# PocaSynth.net
KiCad netlist of a schematic drawn in EAGLE
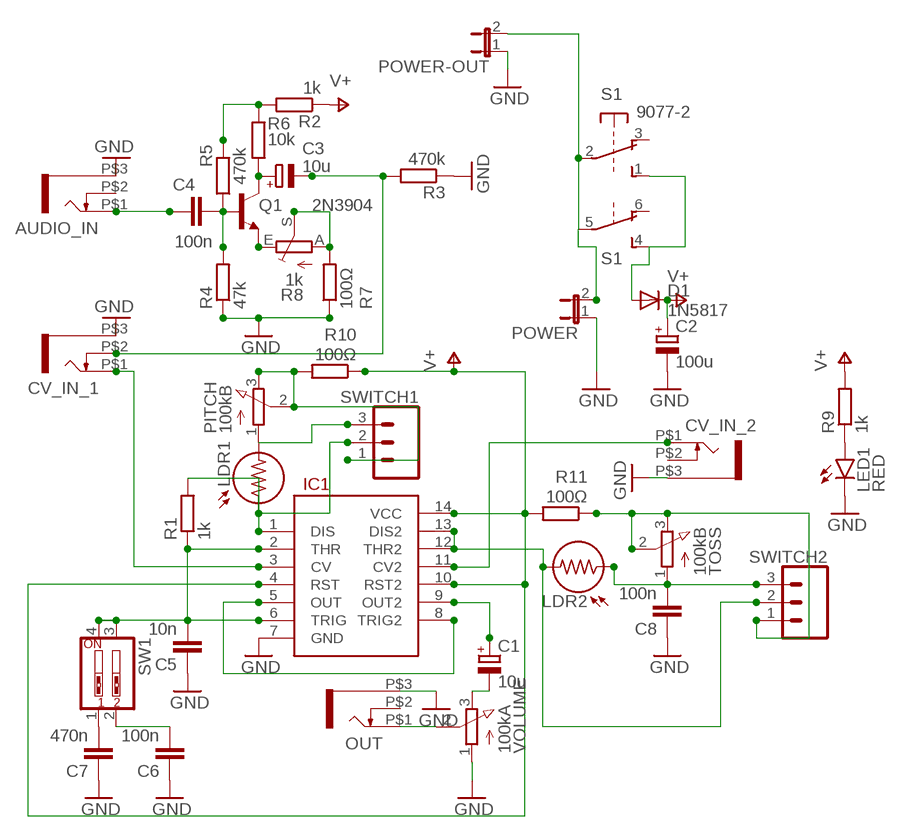
[diagram p0: schematic, sheet 1]

(export (version "E")
  (design (tool "Eeschema 10.0.6"))
  (components
    (comp (ref "AUDIO_IN")
      (value "WQP-PJ301M-12_JACK")
      (footprint "eagle-import:WQP-PJ301M-12_JACK")
      (libsource (lib "eagle-import") (part "WQP-PJ301M-12_JACK"))
    )
    (comp (ref "C1")
      (value "10u")
      (footprint "eagle-import:E2,5-7")
      (libsource (lib "eagle-import") (part "CPOL-EUE2.5-7"))
    )
    (comp (ref "C2")
      (value "100u")
      (footprint "eagle-import:E2,5-7")
      (libsource (lib "eagle-import") (part "CPOL-EUE2.5-7"))
    )
    (comp (ref "C3")
      (value "10u")
      (footprint "eagle-import:E2,5-7")
      (libsource (lib "eagle-import") (part "CPOL-EUE2.5-7"))
    )
    (comp (ref "C4")
      (value "100n")
      (footprint "eagle-import:C050-035X075")
      (libsource (lib "eagle-import") (part "C-EU050-035X075"))
    )
    (comp (ref "C5")
      (value "10n")
      (footprint "eagle-import:C050-030X075")
      (libsource (lib "eagle-import") (part "C-EU050-030X075"))
    )
    (comp (ref "C6")
      (value "100n")
      (footprint "eagle-import:C050-030X075")
      (libsource (lib "eagle-import") (part "C-EU050-030X075"))
    )
    (comp (ref "C7")
      (value "470n")
      (footprint "eagle-import:C050-035X075")
      (libsource (lib "eagle-import") (part "C-EU050-035X075"))
    )
    (comp (ref "C8")
      (value "100n")
      (footprint "eagle-import:C050-030X075")
      (libsource (lib "eagle-import") (part "C-EU050-030X075"))
    )
    (comp (ref "CV_IN_1")
      (value "WQP-PJ301M-12_JACK")
      (footprint "eagle-import:WQP-PJ301M-12_JACK")
      (libsource (lib "eagle-import") (part "WQP-PJ301M-12_JACK"))
    )
    (comp (ref "CV_IN_2")
      (value "WQP-PJ301M-12_JACK")
      (footprint "eagle-import:WQP-PJ301M-12_JACK")
      (libsource (lib "eagle-import") (part "WQP-PJ301M-12_JACK"))
    )
    (comp (ref "D1")
      (value "1N5817")
      (footprint "eagle-import:DO41-10")
      (libsource (lib "eagle-import") (part "1N4004"))
    )
    (comp (ref "IC1")
      (value "556")
      (footprint "eagle-import:DIL14")
      (libsource (lib "eagle-import") (part "556"))
    )
    (comp (ref "LDR1")
      (value "LDR5MM")
      (footprint "eagle-import:LDR338-54C")
      (libsource (lib "eagle-import") (part "LDR5MM"))
    )
    (comp (ref "LDR2")
      (value "LDR5MM")
      (footprint "eagle-import:LDR338-54C")
      (libsource (lib "eagle-import") (part "LDR5MM"))
    )
    (comp (ref "LED1")
      (value "RED")
      (footprint "eagle-import:LED3MM")
      (libsource (lib "eagle-import") (part "LED3MM"))
    )
    (comp (ref "OUT")
      (value "WQP-PJ301M-12_JACK")
      (footprint "eagle-import:WQP-PJ301M-12_JACK")
      (libsource (lib "eagle-import") (part "WQP-PJ301M-12_JACK"))
    )
    (comp (ref "PITCH")
      (value "100kB")
      (footprint "eagle-import:EVUFXM")
      (libsource (lib "eagle-import") (part "EVUMF3"))
    )
    (comp (ref "POWER")
      (value "JP1E")
      (footprint "eagle-import:JP1")
      (libsource (lib "eagle-import") (part "JP1E"))
    )
    (comp (ref "POWER-OUT")
      (value "JP1E")
      (footprint "eagle-import:JP1")
      (libsource (lib "eagle-import") (part "JP1E"))
    )
    (comp (ref "Q1")
      (value "2N3904")
      (footprint "eagle-import:TO92-")
      (libsource (lib "eagle-import") (part "2N3904"))
    )
    (comp (ref "R1")
      (value "1k")
      (footprint "eagle-import:0207_10")
      (libsource (lib "eagle-import") (part "R-EU_0207/10"))
    )
    (comp (ref "R2")
      (value "1k")
      (footprint "eagle-import:0207_10")
      (libsource (lib "eagle-import") (part "R-EU_0207/10"))
    )
    (comp (ref "R3")
      (value "470k")
      (footprint "eagle-import:0207_10")
      (libsource (lib "eagle-import") (part "R-EU_0207/10"))
    )
    (comp (ref "R4")
      (value "47k")
      (footprint "eagle-import:0207_10")
      (libsource (lib "eagle-import") (part "R-EU_0207/10"))
    )
    (comp (ref "R5")
      (value "470k")
      (footprint "eagle-import:0207_10")
      (libsource (lib "eagle-import") (part "R-EU_0207/10"))
    )
    (comp (ref "R6")
      (value "10k")
      (footprint "eagle-import:0207_10")
      (libsource (lib "eagle-import") (part "R-EU_0207/10"))
    )
    (comp (ref "R7")
      (value "100Ω")
      (footprint "eagle-import:0207_10")
      (libsource (lib "eagle-import") (part "R-EU_0207/10"))
    )
    (comp (ref "R8")
      (value "1k")
      (footprint "eagle-import:CA6V")
      (libsource (lib "eagle-import") (part "TRIM_EU-CA6V"))
    )
    (comp (ref "R9")
      (value "1k")
      (footprint "eagle-import:0207_10")
      (libsource (lib "eagle-import") (part "R-EU_0207/10"))
    )
    (comp (ref "R10")
      (value "100Ω")
      (footprint "eagle-import:0207_10")
      (libsource (lib "eagle-import") (part "R-EU_0207/10"))
    )
    (comp (ref "R11")
      (value "100Ω")
      (footprint "eagle-import:0207_10")
      (libsource (lib "eagle-import") (part "R-EU_0207/10"))
    )
    (comp (ref "S1")
      (value "9077-2")
      (footprint "eagle-import:9077-2")
      (libsource (lib "eagle-import") (part "9077-2"))
    )
    (comp (ref "SW1")
      (value "SW_DIP-2")
      (footprint "eagle-import:EDG-02")
      (libsource (lib "eagle-import") (part "SW_DIP-2"))
    )
    (comp (ref "SWITCH1")
      (value "CONN_03LOCK")
      (footprint "eagle-import:1X03_LOCK")
      (libsource (lib "eagle-import") (part "CONN_03LOCK"))
    )
    (comp (ref "SWITCH2")
      (value "CONN_03LOCK")
      (footprint "eagle-import:1X03_LOCK")
      (libsource (lib "eagle-import") (part "CONN_03LOCK"))
    )
    (comp (ref "TOSS")
      (value "100kB")
      (footprint "eagle-import:EVUFXM")
      (libsource (lib "eagle-import") (part "EVUMF3"))
    )
    (comp (ref "VOLUME")
      (value "100kA")
      (footprint "eagle-import:EVUFXM")
      (libsource (lib "eagle-import") (part "EVUMF3"))
    )
  )
  (nets
    (net (code "1") (name "GND") (class "Default")
      (node (ref "AUDIO_IN") (pin "P$3") (pinfunction "1_P$3") (pintype "passive"))
      (node (ref "C2") (pin "-") (pinfunction "-_-") (pintype "passive"))
      (node (ref "C5") (pin "1") (pinfunction "1_1") (pintype "passive"))
      (node (ref "C6") (pin "1") (pinfunction "1_1") (pintype "passive"))
      (node (ref "C7") (pin "1") (pinfunction "1_1") (pintype "passive"))
      (node (ref "C8") (pin "1") (pinfunction "1_1") (pintype "passive"))
      (node (ref "CV_IN_1") (pin "P$3") (pinfunction "1_P$3") (pintype "passive"))
      (node (ref "CV_IN_2") (pin "P$3") (pinfunction "1_P$3") (pintype "passive"))
      (node (ref "IC1") (pin "7") (pinfunction "GND_7") (pintype "bidirectional"))
      (node (ref "LED1") (pin "K") (pinfunction "C_K") (pintype "passive"))
      (node (ref "OUT") (pin "P$3") (pinfunction "1_P$3") (pintype "passive"))
      (node (ref "POWER") (pin "1") (pinfunction "1_1") (pintype "passive"))
      (node (ref "POWER-OUT") (pin "1") (pinfunction "1_1") (pintype "passive"))
      (node (ref "R3") (pin "1") (pinfunction "1_1") (pintype "passive"))
      (node (ref "R4") (pin "1") (pinfunction "1_1") (pintype "passive"))
      (node (ref "R7") (pin "1") (pinfunction "1_1") (pintype "passive"))
      (node (ref "VOLUME") (pin "1") (pinfunction "A_1") (pintype "passive"))
    )
    (net (code "2") (name "Net-(AUDIO_IN-2)") (class "Default")
      (node (ref "AUDIO_IN") (pin "P$1") (pinfunction "2_P$1") (pintype "passive"))
      (node (ref "C4") (pin "1") (pinfunction "1_1") (pintype "passive"))
    )
    (net (code "3") (name "Net-(C6-Pad2)") (class "Default")
      (node (ref "C6") (pin "2") (pinfunction "2_2") (pintype "passive"))
      (node (ref "SW1") (pin "2") (pinfunction "2_2") (pintype "passive"))
    )
    (net (code "4") (name "Net-(C7-Pad2)") (class "Default")
      (node (ref "C7") (pin "2") (pinfunction "2_2") (pintype "passive"))
      (node (ref "SW1") (pin "1") (pinfunction "1_1") (pintype "passive"))
    )
    (net (code "5") (name "Net-(CV_IN_1-2)") (class "Default")
      (node (ref "CV_IN_1") (pin "P$1") (pinfunction "2_P$1") (pintype "passive"))
      (node (ref "IC1") (pin "3") (pinfunction "CV_3") (pintype "bidirectional"))
    )
    (net (code "6") (name "Net-(CV_IN_1-3)") (class "Default")
      (node (ref "C3") (pin "-") (pinfunction "-_-") (pintype "passive"))
      (node (ref "CV_IN_1") (pin "P$2") (pinfunction "3_P$2") (pintype "passive"))
      (node (ref "R3") (pin "2") (pinfunction "2_2") (pintype "passive"))
    )
    (net (code "7") (name "Net-(CV_IN_2-2)") (class "Default")
      (node (ref "CV_IN_2") (pin "P$1") (pinfunction "2_P$1") (pintype "passive"))
      (node (ref "IC1") (pin "11") (pinfunction "CV2_11") (pintype "bidirectional"))
    )
    (net (code "8") (name "Net-(IC1-DIS)") (class "Default")
      (node (ref "IC1") (pin "1") (pinfunction "DIS_1") (pintype "bidirectional"))
      (node (ref "LDR1") (pin "1") (pinfunction "1_1") (pintype "passive"))
      (node (ref "R1") (pin "2") (pinfunction "2_2") (pintype "passive"))
      (node (ref "SWITCH1") (pin "2") (pinfunction "2_2") (pintype "passive"))
    )
    (net (code "9") (name "Net-(IC1-DIS2)") (class "Default")
      (node (ref "IC1") (pin "12") (pinfunction "THR2_12") (pintype "bidirectional"))
      (node (ref "IC1") (pin "13") (pinfunction "DIS2_13") (pintype "bidirectional"))
      (node (ref "LDR2") (pin "2") (pinfunction "2_2") (pintype "passive"))
      (node (ref "SWITCH2") (pin "2") (pinfunction "2_2") (pintype "passive"))
    )
    (net (code "10") (name "Net-(IC1-OUT)") (class "Default")
      (node (ref "IC1") (pin "5") (pinfunction "OUT_5") (pintype "bidirectional"))
      (node (ref "IC1") (pin "8") (pinfunction "TRIG2_8") (pintype "bidirectional"))
    )
    (net (code "11") (name "Net-(IC1-OUT2)") (class "Default")
      (node (ref "C1") (pin "+") (pinfunction "+_+") (pintype "passive"))
      (node (ref "IC1") (pin "9") (pinfunction "OUT2_9") (pintype "bidirectional"))
    )
    (net (code "12") (name "Net-(IC1-THR)") (class "Default")
      (node (ref "C5") (pin "2") (pinfunction "2_2") (pintype "passive"))
      (node (ref "IC1") (pin "2") (pinfunction "THR_2") (pintype "bidirectional"))
      (node (ref "IC1") (pin "6") (pinfunction "TRIG_6") (pintype "bidirectional"))
      (node (ref "R1") (pin "1") (pinfunction "1_1") (pintype "passive"))
      (node (ref "SW1") (pin "3") (pinfunction "3_3") (pintype "passive"))
      (node (ref "SW1") (pin "4") (pinfunction "4_4") (pintype "passive"))
    )
    (net (code "13") (name "Net-(LED1-PadA)") (class "Default")
      (node (ref "LED1") (pin "A") (pinfunction "A_A") (pintype "passive"))
      (node (ref "R9") (pin "1") (pinfunction "1_1") (pintype "passive"))
    )
    (net (code "14") (name "Net-(OUT-2)") (class "Default")
      (node (ref "OUT") (pin "P$1") (pinfunction "2_P$1") (pintype "passive"))
      (node (ref "VOLUME") (pin "2") (pinfunction "S_2") (pintype "passive"))
    )
    (net (code "15") (name "Net-(PITCH-A)") (class "Default")
      (node (ref "LDR1") (pin "2") (pinfunction "2_2") (pintype "passive"))
      (node (ref "PITCH") (pin "1") (pinfunction "A_1") (pintype "passive"))
      (node (ref "SWITCH1") (pin "3") (pinfunction "3_3") (pintype "passive"))
    )
    (net (code "16") (name "Net-(PITCH-E)") (class "Default")
      (node (ref "PITCH") (pin "2") (pinfunction "S_2") (pintype "passive"))
      (node (ref "PITCH") (pin "3") (pinfunction "E_3") (pintype "passive"))
      (node (ref "R10") (pin "2") (pinfunction "2_2") (pintype "passive"))
      (node (ref "SWITCH1") (pin "1") (pinfunction "1_1") (pintype "passive"))
    )
    (net (code "17") (name "Net-(Q1-B)") (class "Default")
      (node (ref "C4") (pin "2") (pinfunction "2_2") (pintype "passive"))
      (node (ref "Q1") (pin "2") (pinfunction "B_2") (pintype "passive"))
      (node (ref "R4") (pin "2") (pinfunction "2_2") (pintype "passive"))
      (node (ref "R5") (pin "1") (pinfunction "1_1") (pintype "passive"))
    )
    (net (code "18") (name "Net-(Q1-C)") (class "Default")
      (node (ref "C3") (pin "+") (pinfunction "+_+") (pintype "passive"))
      (node (ref "Q1") (pin "1") (pinfunction "C_1") (pintype "passive"))
      (node (ref "R6") (pin "1") (pinfunction "1_1") (pintype "passive"))
    )
    (net (code "19") (name "Net-(Q1-E)") (class "Default")
      (node (ref "Q1") (pin "3") (pinfunction "E_3") (pintype "passive"))
      (node (ref "R8") (pin "E") (pinfunction "E_E") (pintype "passive"))
    )
    (net (code "20") (name "Net-(R2-Pad2)") (class "Default")
      (node (ref "R2") (pin "2") (pinfunction "2_2") (pintype "passive"))
      (node (ref "R5") (pin "2") (pinfunction "2_2") (pintype "passive"))
      (node (ref "R6") (pin "2") (pinfunction "2_2") (pintype "passive"))
    )
    (net (code "21") (name "Net-(R7-Pad2)") (class "Default")
      (node (ref "R7") (pin "2") (pinfunction "2_2") (pintype "passive"))
      (node (ref "R8") (pin "A") (pinfunction "A_A") (pintype "passive"))
      (node (ref "R8") (pin "S") (pinfunction "S_S") (pintype "passive"))
    )
    (net (code "22") (name "Net-(S1A-P)") (class "Default")
      (node (ref "POWER") (pin "2") (pinfunction "2_2") (pintype "passive"))
      (node (ref "POWER-OUT") (pin "2") (pinfunction "2_2") (pintype "passive"))
      (node (ref "S1") (pin "2") (pinfunction "P_2") (pintype "passive"))
      (node (ref "S1") (pin "5") (pinfunction "P_5") (pintype "passive"))
    )
    (net (code "23") (name "Net-(S1A-S)") (class "Default")
      (node (ref "D1") (pin "A") (pinfunction "A_A") (pintype "passive"))
      (node (ref "S1") (pin "1") (pinfunction "S_1") (pintype "passive"))
      (node (ref "S1") (pin "4") (pinfunction "S_4") (pintype "passive"))
    )
    (net (code "24") (name "Net-(TOSS-A)") (class "Default")
      (node (ref "C8") (pin "2") (pinfunction "2_2") (pintype "passive"))
      (node (ref "LDR2") (pin "1") (pinfunction "1_1") (pintype "passive"))
      (node (ref "SWITCH2") (pin "3") (pinfunction "3_3") (pintype "passive"))
      (node (ref "TOSS") (pin "1") (pinfunction "A_1") (pintype "passive"))
    )
    (net (code "25") (name "Net-(TOSS-E)") (class "Default")
      (node (ref "R11") (pin "1") (pinfunction "1_1") (pintype "passive"))
      (node (ref "SWITCH2") (pin "1") (pinfunction "1_1") (pintype "passive"))
      (node (ref "TOSS") (pin "2") (pinfunction "S_2") (pintype "passive"))
      (node (ref "TOSS") (pin "3") (pinfunction "E_3") (pintype "passive"))
    )
    (net (code "26") (name "Net-(VOLUME-E)") (class "Default")
      (node (ref "C1") (pin "-") (pinfunction "-_-") (pintype "passive"))
      (node (ref "VOLUME") (pin "3") (pinfunction "E_3") (pintype "passive"))
    )
    (net (code "27") (name "V+") (class "Default")
      (node (ref "C2") (pin "+") (pinfunction "+_+") (pintype "passive"))
      (node (ref "D1") (pin "C") (pinfunction "C_C") (pintype "passive"))
      (node (ref "IC1") (pin "10") (pinfunction "RST2_10") (pintype "bidirectional"))
      (node (ref "IC1") (pin "14") (pinfunction "VCC_14") (pintype "bidirectional"))
      (node (ref "IC1") (pin "4") (pinfunction "RST_4") (pintype "bidirectional"))
      (node (ref "R10") (pin "1") (pinfunction "1_1") (pintype "passive"))
      (node (ref "R11") (pin "2") (pinfunction "2_2") (pintype "passive"))
      (node (ref "R2") (pin "1") (pinfunction "1_1") (pintype "passive"))
      (node (ref "R9") (pin "2") (pinfunction "2_2") (pintype "passive"))
    )
    (net (code "28") (name "unconnected-(AUDIO_IN-3-PadP$2)") (class "Default")
      (node (ref "AUDIO_IN") (pin "P$2") (pinfunction "3_P$2") (pintype "passive"))
    )
    (net (code "29") (name "unconnected-(CV_IN_2-3-PadP$2)") (class "Default")
      (node (ref "CV_IN_2") (pin "P$2") (pinfunction "3_P$2") (pintype "passive"))
    )
    (net (code "30") (name "unconnected-(OUT-3-PadP$2)") (class "Default")
      (node (ref "OUT") (pin "P$2") (pinfunction "3_P$2") (pintype "passive"))
    )
    (net (code "31") (name "unconnected-(S1A-O-Pad3)") (class "Default")
      (node (ref "S1") (pin "3") (pinfunction "O_3") (pintype "passive"))
    )
    (net (code "32") (name "unconnected-(S1B-O-Pad6)") (class "Default")
      (node (ref "S1") (pin "6") (pinfunction "O_6") (pintype "passive"))
    )
  )
)
